# ME433_Spring2017.net
KiCad netlist of a schematic drawn in EAGLE
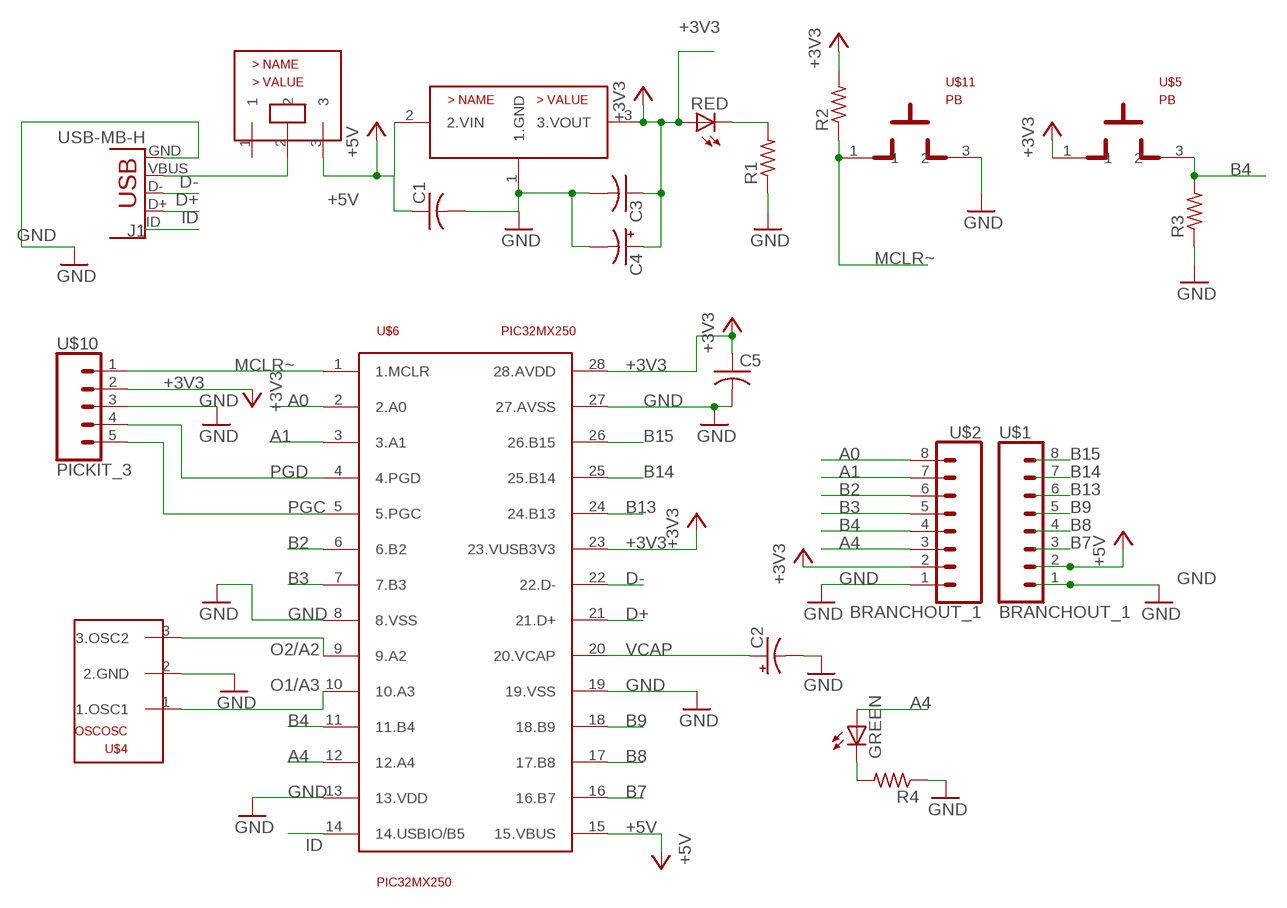
[diagram p0: schematic, sheet 1]

(export (version "E")
  (design (tool "Eeschema 10.0.6"))
  (components
    (comp (ref "C1")
      (value "C-US025-025X050")
      (footprint "eagle-import:C025-025X050")
      (libsource (lib "eagle-import") (part "C-US025-025X050"))
    )
    (comp (ref "C2")
      (value "CPOL-USB45181B")
      (footprint "eagle-import:B45181B")
      (libsource (lib "eagle-import") (part "CPOL-USB45181B"))
    )
    (comp (ref "C3")
      (value "C-US025-025X050")
      (footprint "eagle-import:C025-025X050")
      (libsource (lib "eagle-import") (part "C-US025-025X050"))
    )
    (comp (ref "C4")
      (value "CPOL-USB45181B")
      (footprint "eagle-import:B45181B")
      (libsource (lib "eagle-import") (part "CPOL-USB45181B"))
    )
    (comp (ref "C5")
      (value "C-US025-025X050")
      (footprint "eagle-import:C025-025X050")
      (libsource (lib "eagle-import") (part "C-US025-025X050"))
    )
    (comp (ref "GREEN")
      (value "LED3MM")
      (footprint "eagle-import:LED3MM")
      (libsource (lib "eagle-import") (part "LED3MM"))
    )
    (comp (ref "J1")
      (value "USB-MB-H")
      (footprint "eagle-import:USB-MB-H")
      (libsource (lib "eagle-import") (part "USB-MB-H"))
    )
    (comp (ref "R1")
      (value "R-US_0204/7")
      (footprint "eagle-import:0204_7")
      (libsource (lib "eagle-import") (part "R-US_0204/7"))
    )
    (comp (ref "R2")
      (value "R-US_0204/7")
      (footprint "eagle-import:0204_7")
      (libsource (lib "eagle-import") (part "R-US_0204/7"))
    )
    (comp (ref "R3")
      (value "R-US_0204/7")
      (footprint "eagle-import:0204_7")
      (libsource (lib "eagle-import") (part "R-US_0204/7"))
    )
    (comp (ref "R4")
      (value "R-US_0204/7")
      (footprint "eagle-import:0204_7")
      (libsource (lib "eagle-import") (part "R-US_0204/7"))
    )
    (comp (ref "RED")
      (value "LED3MM")
      (footprint "eagle-import:LED3MM")
      (libsource (lib "eagle-import") (part "LED3MM"))
    )
    (comp (ref "U$1")
      (value "BRANCHOUT_1")
      (footprint "eagle-import:1X08")
      (libsource (lib "eagle-import") (part "BRANCHOUT_1"))
    )
    (comp (ref "U$2")
      (value "BRANCHOUT_1")
      (footprint "eagle-import:1X08")
      (libsource (lib "eagle-import") (part "BRANCHOUT_1"))
    )
    (comp (ref "U$4")
      (value "OSCOSC")
      (footprint "eagle-import:OSC")
      (libsource (lib "eagle-import") (part "OSCOSC"))
    )
    (comp (ref "U$5") (value "PB") (footprint "eagle-import:PB") (libsource (lib "eagle-import") (part "PB")))
    (comp (ref "U$6")
      (value "PIC32MX250")
      (footprint "eagle-import:DIL28-3")
      (libsource (lib "eagle-import") (part "PIC32MX250"))
    )
    (comp (ref "U$8")
      (value "SLIDE")
      (footprint "eagle-import:SLIDE")
      (libsource (lib "eagle-import") (part "SLIDE"))
    )
    (comp (ref "U$10")
      (value "PICKIT_3")
      (footprint "eagle-import:1X05")
      (libsource (lib "eagle-import") (part "PICKIT_3"))
    )
    (comp (ref "U$11")
      (value "PB")
      (footprint "eagle-import:PB")
      (libsource (lib "eagle-import") (part "PB"))
    )
    (comp (ref "_")
      (value "MCP1702")
      (footprint "eagle-import:TO92")
      (libsource (lib "eagle-import") (part "MCP1702"))
    )
  )
  (nets
    (net (code "1") (name "+3V3") (class "Default")
      (node (ref "C3") (pin "1") (pinfunction "1_1") (pintype "passive"))
      (node (ref "C4") (pin "+") (pinfunction "+_+") (pintype "passive"))
      (node (ref "C5") (pin "1") (pinfunction "1_1") (pintype "passive"))
      (node (ref "R2") (pin "2") (pinfunction "2_2") (pintype "passive"))
      (node (ref "RED") (pin "A") (pinfunction "A_A") (pintype "passive"))
      (node (ref "U$10") (pin "2") (pinfunction "2.VDD_2") (pintype "passive"))
      (node (ref "U$2") (pin "2") (pinfunction "2_2") (pintype "passive"))
      (node (ref "U$5") (pin "1") (pinfunction "1_1") (pintype "bidirectional"))
      (node (ref "U$6") (pin "23") (pinfunction "23.VUSB3V3_23") (pintype "bidirectional"))
      (node (ref "U$6") (pin "28") (pinfunction "28.AVDD_28") (pintype "bidirectional"))
      (node (ref "_") (pin "3") (pinfunction "3.VOUT_3") (pintype "bidirectional"))
    )
    (net (code "2") (name "+5V") (class "Default")
      (node (ref "C1") (pin "1") (pinfunction "1_1") (pintype "passive"))
      (node (ref "U$1") (pin "2") (pinfunction "2_2") (pintype "passive"))
      (node (ref "U$6") (pin "15") (pinfunction "15.VBUS_15") (pintype "bidirectional"))
      (node (ref "U$8") (pin "3") (pinfunction "3_3") (pintype "bidirectional"))
      (node (ref "_") (pin "2") (pinfunction "2.VIN_2") (pintype "bidirectional"))
    )
    (net (code "3") (name "/A0") (class "Default")
      (node (ref "U$2") (pin "8") (pinfunction "8_8") (pintype "passive"))
      (node (ref "U$6") (pin "2") (pinfunction "2.A0_2") (pintype "bidirectional"))
    )
    (net (code "4") (name "/A1") (class "Default")
      (node (ref "U$2") (pin "7") (pinfunction "7_7") (pintype "passive"))
      (node (ref "U$6") (pin "3") (pinfunction "3.A1_3") (pintype "bidirectional"))
    )
    (net (code "5") (name "/A4") (class "Default")
      (node (ref "GREEN") (pin "A") (pinfunction "A_A") (pintype "passive"))
      (node (ref "U$2") (pin "3") (pinfunction "3_3") (pintype "passive"))
      (node (ref "U$6") (pin "12") (pinfunction "12.A4_12") (pintype "bidirectional"))
    )
    (net (code "6") (name "/B2") (class "Default")
      (node (ref "U$2") (pin "6") (pinfunction "6_6") (pintype "passive"))
      (node (ref "U$6") (pin "6") (pinfunction "6.B2_6") (pintype "bidirectional"))
    )
    (net (code "7") (name "/B3") (class "Default")
      (node (ref "U$2") (pin "5") (pinfunction "5_5") (pintype "passive"))
      (node (ref "U$6") (pin "7") (pinfunction "7.B3_7") (pintype "bidirectional"))
    )
    (net (code "8") (name "/B4") (class "Default")
      (node (ref "R3") (pin "2") (pinfunction "2_2") (pintype "passive"))
      (node (ref "U$2") (pin "4") (pinfunction "4_4") (pintype "passive"))
      (node (ref "U$5") (pin "3") (pinfunction "2_3") (pintype "bidirectional"))
      (node (ref "U$6") (pin "11") (pinfunction "11.B4_11") (pintype "bidirectional"))
    )
    (net (code "9") (name "/B7") (class "Default")
      (node (ref "U$1") (pin "3") (pinfunction "3_3") (pintype "passive"))
      (node (ref "U$6") (pin "16") (pinfunction "16.B7_16") (pintype "bidirectional"))
    )
    (net (code "10") (name "/B8") (class "Default")
      (node (ref "U$1") (pin "4") (pinfunction "4_4") (pintype "passive"))
      (node (ref "U$6") (pin "17") (pinfunction "17.B8_17") (pintype "bidirectional"))
    )
    (net (code "11") (name "/B9") (class "Default")
      (node (ref "U$1") (pin "5") (pinfunction "5_5") (pintype "passive"))
      (node (ref "U$6") (pin "18") (pinfunction "18.B9_18") (pintype "bidirectional"))
    )
    (net (code "12") (name "/B13") (class "Default")
      (node (ref "U$1") (pin "6") (pinfunction "6_6") (pintype "passive"))
      (node (ref "U$6") (pin "24") (pinfunction "24.B13_24") (pintype "bidirectional"))
    )
    (net (code "13") (name "/B14") (class "Default")
      (node (ref "U$1") (pin "7") (pinfunction "7_7") (pintype "passive"))
      (node (ref "U$6") (pin "25") (pinfunction "25.B14_25") (pintype "bidirectional"))
    )
    (net (code "14") (name "/B15") (class "Default")
      (node (ref "U$1") (pin "8") (pinfunction "8_8") (pintype "passive"))
      (node (ref "U$6") (pin "26") (pinfunction "26.B15_26") (pintype "bidirectional"))
    )
    (net (code "15") (name "/D+") (class "Default")
      (node (ref "J1") (pin "D+") (pinfunction "D+_D+") (pintype "bidirectional"))
      (node (ref "U$6") (pin "21") (pinfunction "21.D+_21") (pintype "bidirectional"))
    )
    (net (code "16") (name "/D-") (class "Default")
      (node (ref "J1") (pin "D-") (pinfunction "D-_D-") (pintype "bidirectional"))
      (node (ref "U$6") (pin "22") (pinfunction "22.D-_22") (pintype "bidirectional"))
    )
    (net (code "17") (name "/ID") (class "Default")
      (node (ref "J1") (pin "ID") (pinfunction "ID_ID") (pintype "bidirectional"))
      (node (ref "U$6") (pin "14") (pinfunction "14.USBIO/B5_14") (pintype "bidirectional"))
    )
    (net (code "18") (name "/MCLR~{}") (class "Default")
      (node (ref "R2") (pin "1") (pinfunction "1_1") (pintype "passive"))
      (node (ref "U$10") (pin "1") (pinfunction "1.MCLR~{}_1") (pintype "passive"))
      (node (ref "U$11") (pin "1") (pinfunction "1_1") (pintype "bidirectional"))
      (node (ref "U$6") (pin "1") (pinfunction "1.MCLR_1") (pintype "bidirectional"))
    )
    (net (code "19") (name "/O1{slash}A3") (class "Default")
      (node (ref "U$4") (pin "1") (pinfunction "1.OSC1_1") (pintype "bidirectional"))
      (node (ref "U$6") (pin "10") (pinfunction "10.A3_10") (pintype "bidirectional"))
    )
    (net (code "20") (name "/O2{slash}A2") (class "Default")
      (node (ref "U$4") (pin "3") (pinfunction "3.OSC2_3") (pintype "bidirectional"))
      (node (ref "U$6") (pin "9") (pinfunction "9.A2_9") (pintype "bidirectional"))
    )
    (net (code "21") (name "/PGC") (class "Default")
      (node (ref "U$10") (pin "5") (pinfunction "5.PGC_5") (pintype "passive"))
      (node (ref "U$6") (pin "5") (pinfunction "5.PGC_5") (pintype "bidirectional"))
    )
    (net (code "22") (name "/PGD") (class "Default")
      (node (ref "U$10") (pin "4") (pinfunction "4.PGD_4") (pintype "passive"))
      (node (ref "U$6") (pin "4") (pinfunction "4.PGD_4") (pintype "bidirectional"))
    )
    (net (code "23") (name "/VCAP") (class "Default")
      (node (ref "C2") (pin "+") (pinfunction "+_+") (pintype "passive"))
      (node (ref "U$6") (pin "20") (pinfunction "20.VCAP_20") (pintype "bidirectional"))
    )
    (net (code "24") (name "GND") (class "Default")
      (node (ref "C1") (pin "2") (pinfunction "2_2") (pintype "passive"))
      (node (ref "C2") (pin "-") (pinfunction "-_-") (pintype "passive"))
      (node (ref "C3") (pin "2") (pinfunction "2_2") (pintype "passive"))
      (node (ref "C4") (pin "-") (pinfunction "-_-") (pintype "passive"))
      (node (ref "C5") (pin "2") (pinfunction "2_2") (pintype "passive"))
      (node (ref "J1") (pin "GND") (pinfunction "GND_GND") (pintype "bidirectional"))
      (node (ref "R1") (pin "1") (pinfunction "1_1") (pintype "passive"))
      (node (ref "R3") (pin "1") (pinfunction "1_1") (pintype "passive"))
      (node (ref "R4") (pin "1") (pinfunction "1_1") (pintype "passive"))
      (node (ref "U$1") (pin "1") (pinfunction "1_1") (pintype "passive"))
      (node (ref "U$10") (pin "3") (pinfunction "3.VSS_3") (pintype "passive"))
      (node (ref "U$11") (pin "3") (pinfunction "2_3") (pintype "bidirectional"))
      (node (ref "U$2") (pin "1") (pinfunction "1_1") (pintype "passive"))
      (node (ref "U$4") (pin "2") (pinfunction "2.GND_2") (pintype "bidirectional"))
      (node (ref "U$6") (pin "13") (pinfunction "13.VDD_13") (pintype "bidirectional"))
      (node (ref "U$6") (pin "19") (pinfunction "19.VSS_19") (pintype "bidirectional"))
      (node (ref "U$6") (pin "27") (pinfunction "27.AVSS_27") (pintype "bidirectional"))
      (node (ref "U$6") (pin "8") (pinfunction "8.VSS_8") (pintype "bidirectional"))
      (node (ref "_") (pin "1") (pinfunction "1.GND_1") (pintype "bidirectional"))
    )
    (net (code "25") (name "Net-(GREEN-C)") (class "Default")
      (node (ref "GREEN") (pin "K") (pinfunction "C_K") (pintype "passive"))
      (node (ref "R4") (pin "2") (pinfunction "2_2") (pintype "passive"))
    )
    (net (code "26") (name "Net-(J1-PadVBUS)") (class "Default")
      (node (ref "J1") (pin "VBUS") (pinfunction "VBUS_VBUS") (pintype "bidirectional"))
      (node (ref "U$8") (pin "2") (pinfunction "2_2") (pintype "bidirectional"))
    )
    (net (code "27") (name "Net-(RED-C)") (class "Default")
      (node (ref "R1") (pin "2") (pinfunction "2_2") (pintype "passive"))
      (node (ref "RED") (pin "K") (pinfunction "C_K") (pintype "passive"))
    )
    (net (code "28") (name "unconnected-(U$8-Pad1)") (class "Default")
      (node (ref "U$8") (pin "1") (pinfunction "1_1") (pintype "bidirectional"))
    )
  )
)
